# ic2_extention.net
KiCad netlist of a schematic drawn in EAGLE
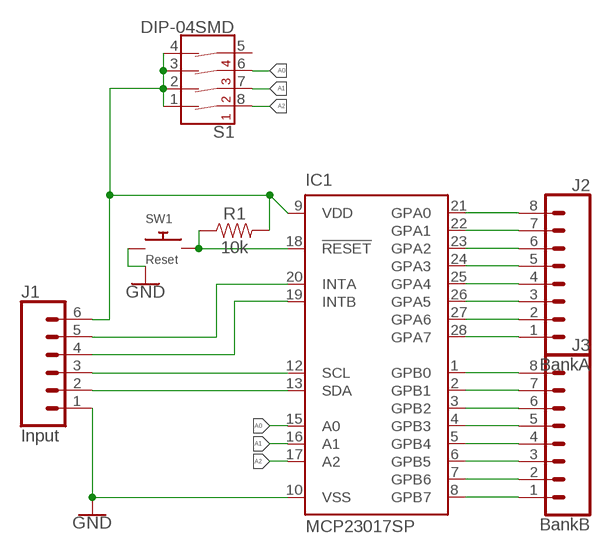
[diagram p0: schematic, sheet 1]

(export (version "E")
  (design (tool "Eeschema 10.0.6"))
  (components
    (comp (ref "IC1")
      (value "MCP23017SP")
      (footprint "eagle-import:DIL28-3")
      (libsource (lib "eagle-import") (part "MCP23017SP"))
    )
    (comp (ref "J1")
      (value "Input")
      (footprint "eagle-import:1X06_LOCK")
      (libsource (lib "eagle-import") (part "CONN_06LOCK"))
    )
    (comp (ref "J2")
      (value "BankA")
      (footprint "eagle-import:1X08")
      (libsource (lib "eagle-import") (part "CONN_08{dblquote}"))
    )
    (comp (ref "J3")
      (value "BankB")
      (footprint "eagle-import:1X08")
      (libsource (lib "eagle-import") (part "CONN_08{dblquote}"))
    )
    (comp (ref "R1")
      (value "10k")
      (footprint "eagle-import:0603")
      (libsource (lib "eagle-import") (part "10KOHM-0603-1/10W-1%"))
    )
    (comp (ref "S1")
      (value "DIP-04SMD")
      (footprint "eagle-import:DIPSWITCH-04-SMD")
      (libsource (lib "eagle-import") (part "DIP-04SMD"))
    )
    (comp (ref "SW1")
      (value "Reset")
      (footprint "eagle-import:BTN_CK_KSS")
      (libsource (lib "eagle-import") (part "SWITCH_PUSHBUTTONC&K_KSS"))
    )
  )
  (nets
    (net (code "1") (name "A0") (class "Default")
      (node (ref "IC1") (pin "15") (pinfunction "A0_15") (pintype "input"))
      (node (ref "S1") (pin "6") (pinfunction "3B_6") (pintype "bidirectional"))
    )
    (net (code "2") (name "A1") (class "Default")
      (node (ref "IC1") (pin "16") (pinfunction "A1_16") (pintype "input"))
      (node (ref "S1") (pin "7") (pinfunction "2B_7") (pintype "bidirectional"))
    )
    (net (code "3") (name "A2") (class "Default")
      (node (ref "IC1") (pin "17") (pinfunction "A2_17") (pintype "input"))
      (node (ref "S1") (pin "8") (pinfunction "1B_8") (pintype "bidirectional"))
    )
    (net (code "4") (name "GND") (class "Default")
      (node (ref "IC1") (pin "10") (pinfunction "VSS_10") (pintype "power_in"))
      (node (ref "J1") (pin "1") (pinfunction "1_1") (pintype "passive"))
      (node (ref "SW1") (pin "P$1") (pinfunction "P$1_P$1") (pintype "passive"))
    )
    (net (code "5") (name "Net-(IC1-GPA0)") (class "Default")
      (node (ref "IC1") (pin "21") (pinfunction "GPA0_21") (pintype "bidirectional"))
      (node (ref "J2") (pin "8") (pinfunction "8_8") (pintype "passive"))
    )
    (net (code "6") (name "Net-(IC1-GPA1)") (class "Default")
      (node (ref "IC1") (pin "22") (pinfunction "GPA1_22") (pintype "bidirectional"))
      (node (ref "J2") (pin "7") (pinfunction "7_7") (pintype "passive"))
    )
    (net (code "7") (name "Net-(IC1-GPA2)") (class "Default")
      (node (ref "IC1") (pin "23") (pinfunction "GPA2_23") (pintype "bidirectional"))
      (node (ref "J2") (pin "6") (pinfunction "6_6") (pintype "passive"))
    )
    (net (code "8") (name "Net-(IC1-GPA3)") (class "Default")
      (node (ref "IC1") (pin "24") (pinfunction "GPA3_24") (pintype "bidirectional"))
      (node (ref "J2") (pin "5") (pinfunction "5_5") (pintype "passive"))
    )
    (net (code "9") (name "Net-(IC1-GPA4)") (class "Default")
      (node (ref "IC1") (pin "25") (pinfunction "GPA4_25") (pintype "bidirectional"))
      (node (ref "J2") (pin "4") (pinfunction "4_4") (pintype "passive"))
    )
    (net (code "10") (name "Net-(IC1-GPA5)") (class "Default")
      (node (ref "IC1") (pin "26") (pinfunction "GPA5_26") (pintype "bidirectional"))
      (node (ref "J2") (pin "3") (pinfunction "3_3") (pintype "passive"))
    )
    (net (code "11") (name "Net-(IC1-GPA6)") (class "Default")
      (node (ref "IC1") (pin "27") (pinfunction "GPA6_27") (pintype "bidirectional"))
      (node (ref "J2") (pin "2") (pinfunction "2_2") (pintype "passive"))
    )
    (net (code "12") (name "Net-(IC1-GPA7)") (class "Default")
      (node (ref "IC1") (pin "28") (pinfunction "GPA7_28") (pintype "bidirectional"))
      (node (ref "J2") (pin "1") (pinfunction "1_1") (pintype "passive"))
    )
    (net (code "13") (name "Net-(IC1-GPB0)") (class "Default")
      (node (ref "IC1") (pin "1") (pinfunction "GPB0_1") (pintype "bidirectional"))
      (node (ref "J3") (pin "8") (pinfunction "8_8") (pintype "passive"))
    )
    (net (code "14") (name "Net-(IC1-GPB1)") (class "Default")
      (node (ref "IC1") (pin "2") (pinfunction "GPB1_2") (pintype "bidirectional"))
      (node (ref "J3") (pin "7") (pinfunction "7_7") (pintype "passive"))
    )
    (net (code "15") (name "Net-(IC1-GPB2)") (class "Default")
      (node (ref "IC1") (pin "3") (pinfunction "GPB2_3") (pintype "bidirectional"))
      (node (ref "J3") (pin "6") (pinfunction "6_6") (pintype "passive"))
    )
    (net (code "16") (name "Net-(IC1-GPB3)") (class "Default")
      (node (ref "IC1") (pin "4") (pinfunction "GPB3_4") (pintype "bidirectional"))
      (node (ref "J3") (pin "5") (pinfunction "5_5") (pintype "passive"))
    )
    (net (code "17") (name "Net-(IC1-GPB4)") (class "Default")
      (node (ref "IC1") (pin "5") (pinfunction "GPB4_5") (pintype "bidirectional"))
      (node (ref "J3") (pin "4") (pinfunction "4_4") (pintype "passive"))
    )
    (net (code "18") (name "Net-(IC1-GPB5)") (class "Default")
      (node (ref "IC1") (pin "6") (pinfunction "GPB5_6") (pintype "bidirectional"))
      (node (ref "J3") (pin "3") (pinfunction "3_3") (pintype "passive"))
    )
    (net (code "19") (name "Net-(IC1-GPB6)") (class "Default")
      (node (ref "IC1") (pin "7") (pinfunction "GPB6_7") (pintype "bidirectional"))
      (node (ref "J3") (pin "2") (pinfunction "2_2") (pintype "passive"))
    )
    (net (code "20") (name "Net-(IC1-GPB7)") (class "Default")
      (node (ref "IC1") (pin "8") (pinfunction "GPB7_8") (pintype "bidirectional"))
      (node (ref "J3") (pin "1") (pinfunction "1_1") (pintype "passive"))
    )
    (net (code "21") (name "Net-(IC1-INTA)") (class "Default")
      (node (ref "IC1") (pin "20") (pinfunction "INTA_20") (pintype "output"))
      (node (ref "J1") (pin "5") (pinfunction "5_5") (pintype "passive"))
    )
    (net (code "22") (name "Net-(IC1-INTB)") (class "Default")
      (node (ref "IC1") (pin "19") (pinfunction "INTB_19") (pintype "output"))
      (node (ref "J1") (pin "4") (pinfunction "4_4") (pintype "passive"))
    )
    (net (code "23") (name "Net-(IC1-SCL)") (class "Default")
      (node (ref "IC1") (pin "12") (pinfunction "SCL_12") (pintype "input"))
      (node (ref "J1") (pin "3") (pinfunction "3_3") (pintype "passive"))
    )
    (net (code "24") (name "Net-(IC1-SDA)") (class "Default")
      (node (ref "IC1") (pin "13") (pinfunction "SDA_13") (pintype "bidirectional"))
      (node (ref "J1") (pin "2") (pinfunction "2_2") (pintype "passive"))
    )
    (net (code "25") (name "Net-(IC1-VDD)") (class "Default")
      (node (ref "IC1") (pin "9") (pinfunction "VDD_9") (pintype "power_in"))
      (node (ref "J1") (pin "6") (pinfunction "6_6") (pintype "passive"))
      (node (ref "R1") (pin "2") (pinfunction "2_2") (pintype "passive"))
      (node (ref "S1") (pin "1") (pinfunction "1A_1") (pintype "bidirectional"))
      (node (ref "S1") (pin "2") (pinfunction "2A_2") (pintype "bidirectional"))
      (node (ref "S1") (pin "3") (pinfunction "3A_3") (pintype "bidirectional"))
      (node (ref "S1") (pin "4") (pinfunction "4A_4") (pintype "bidirectional"))
    )
    (net (code "26") (name "Net-(IC1-~{RESET})") (class "Default")
      (node (ref "IC1") (pin "18") (pinfunction "~{RESET}_18") (pintype "input"))
      (node (ref "R1") (pin "1") (pinfunction "1_1") (pintype "passive"))
      (node (ref "SW1") (pin "P$2") (pinfunction "P$2_P$2") (pintype "passive"))
    )
    (net (code "27") (name "unconnected-(S1-4B-Pad5)") (class "Default")
      (node (ref "S1") (pin "5") (pinfunction "4B_5") (pintype "bidirectional"))
    )
  )
)
